# BellSystem.net
KiCad netlist of a schematic drawn in Altium Designer
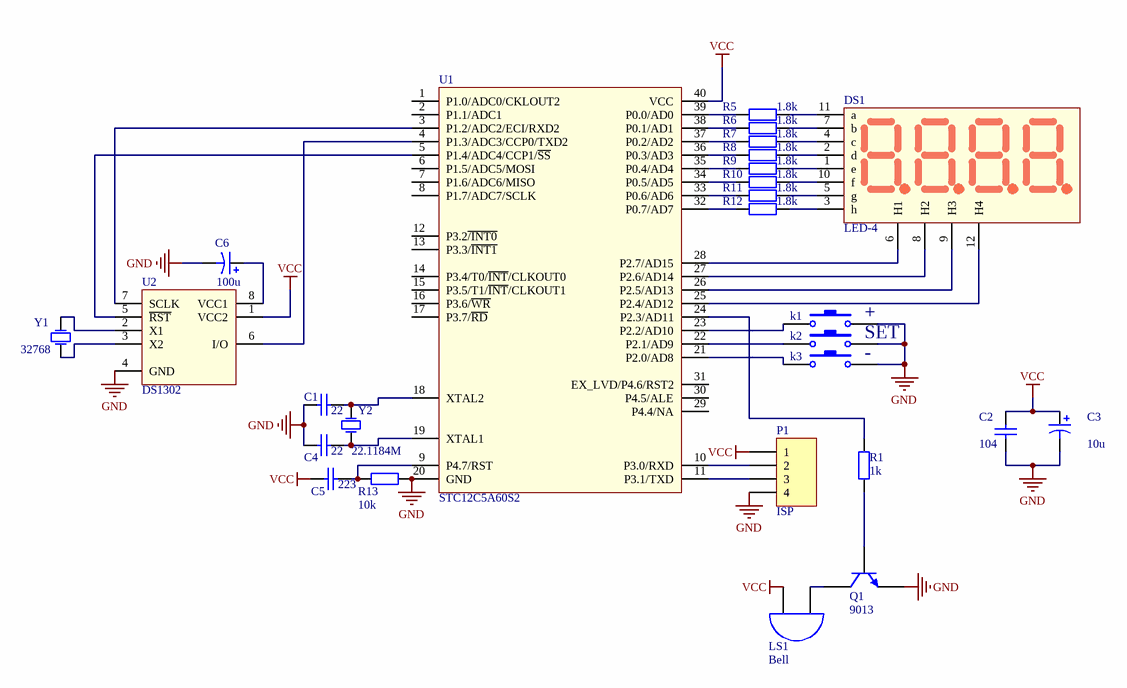
[diagram p0: BellSystem.SchDoc]

(export (version "E")
  (design (tool "Eeschema 10.0.6"))
  (components
    (comp (ref "C1")
      (value "22")
      (footprint "cap")
      (description "Capacitor")
      (fields (field (name "PUBLISHER") "Altium Limited"))
      (libsource (lib "Miscellaneous Devices") (part "Cap"))
    )
    (comp (ref "C2")
      (value "104")
      (footprint "cap")
      (description "Capacitor")
      (fields (field (name "PUBLISHER") "Altium Limited"))
      (libsource (lib "Miscellaneous Devices") (part "Cap"))
    )
    (comp (ref "C3")
      (value "10u")
      (footprint "RB.1/.2")
      (description "Polarized Capacitor (Radial)")
      (fields (field (name "PUBLISHER") "Altium Limited"))
      (libsource (lib "Miscellaneous Devices") (part "Cap Pol1"))
    )
    (comp (ref "C4")
      (value "22")
      (footprint "cap")
      (description "Capacitor")
      (fields (field (name "PUBLISHER") "Altium Limited"))
      (libsource (lib "Miscellaneous Devices") (part "Cap"))
    )
    (comp (ref "C5")
      (value "223")
      (footprint "cap")
      (description "Capacitor")
      (fields (field (name "PUBLISHER") "Altium Limited"))
      (libsource (lib "Miscellaneous Devices") (part "Cap"))
    )
    (comp (ref "C6")
      (value "100u")
      (footprint "RB.1/.2")
      (description "Polarized Capacitor (Radial)")
      (fields (field (name "PUBLISHER") "Altium Limited"))
      (libsource (lib "Miscellaneous Devices") (part "Cap Pol1"))
    )
    (comp (ref "DS1") (value "LED-4") (footprint "7SEG_036x4") (libsource (lib "教学打铃系统") (part "LED-4")))
    (comp (ref "k1")
      (value "+")
      (footprint "SW-4")
      (description "Switch")
      (fields (field (name "PUBLISHER") "Altium Limited"))
      (libsource (lib "Miscellaneous Devices") (part "SW-PB"))
    )
    (comp (ref "k2")
      (value "SET")
      (footprint "SW-4")
      (description "Switch")
      (fields (field (name "PUBLISHER") "Altium Limited"))
      (libsource (lib "Miscellaneous Devices") (part "SW-PB"))
    )
    (comp (ref "k3")
      (value "-")
      (footprint "SW-4")
      (description "Switch")
      (fields (field (name "PUBLISHER") "Altium Limited"))
      (libsource (lib "Miscellaneous Devices") (part "SW-PB"))
    )
    (comp (ref "LS1")
      (value "Bell")
      (footprint "蜂鸣器")
      (description "Electrical Bell")
      (fields (field (name "PUBLISHER") "Altium Limited"))
      (libsource (lib "Miscellaneous Devices") (part "Bell"))
    )
    (comp (ref "P1")
      (value "ISP")
      (footprint "sip4")
      (description "Header, 4-Pin")
      (fields (field (name "PUBLISHER") "Altium Limited"))
      (libsource (lib "Miscellaneous Connectors") (part "Header 4"))
    )
    (comp (ref "Q1")
      (value "9013")
      (footprint "To-92")
      (description "NPN General Purpose Amplifier")
      (fields (field (name "PUBLISHER") "Altium Limited"))
      (libsource (lib "Miscellaneous Devices") (part "2N3904"))
    )
    (comp (ref "R1")
      (value "1k")
      (footprint "AXIAL-0.3")
      (description "Resistor")
      (fields (field (name "PUBLISHER") "Altium Limited"))
      (libsource (lib "Miscellaneous Devices") (part "Res2"))
    )
    (comp (ref "R5")
      (value "1.8k")
      (footprint "AXIAL-0.3")
      (description "Resistor")
      (fields (field (name "PUBLISHER") "Altium Limited"))
      (libsource (lib "") (part "Res2_1"))
    )
    (comp (ref "R6")
      (value "1.8k")
      (footprint "AXIAL-0.3")
      (description "Resistor")
      (fields (field (name "PUBLISHER") "Altium Limited"))
      (libsource (lib "") (part "Res2_1"))
    )
    (comp (ref "R7")
      (value "1.8k")
      (footprint "AXIAL-0.3")
      (description "Resistor")
      (fields (field (name "PUBLISHER") "Altium Limited"))
      (libsource (lib "") (part "Res2_1"))
    )
    (comp (ref "R8")
      (value "1.8k")
      (footprint "AXIAL-0.3")
      (description "Resistor")
      (fields (field (name "PUBLISHER") "Altium Limited"))
      (libsource (lib "") (part "Res2_1"))
    )
    (comp (ref "R9")
      (value "1.8k")
      (footprint "AXIAL-0.3")
      (description "Resistor")
      (fields (field (name "PUBLISHER") "Altium Limited"))
      (libsource (lib "") (part "Res2_1"))
    )
    (comp (ref "R10")
      (value "1.8k")
      (footprint "AXIAL-0.3")
      (description "Resistor")
      (fields (field (name "PUBLISHER") "Altium Limited"))
      (libsource (lib "") (part "Res2_1"))
    )
    (comp (ref "R11")
      (value "1.8k")
      (footprint "AXIAL-0.3")
      (description "Resistor")
      (fields (field (name "PUBLISHER") "Altium Limited"))
      (libsource (lib "") (part "Res2_1"))
    )
    (comp (ref "R12")
      (value "1.8k")
      (footprint "AXIAL-0.3")
      (description "Resistor")
      (fields (field (name "PUBLISHER") "Altium Limited"))
      (libsource (lib "") (part "Res2_1"))
    )
    (comp (ref "R13")
      (value "10k")
      (footprint "AXIAL-0.3")
      (description "Resistor")
      (fields (field (name "PUBLISHER") "Altium Limited"))
      (libsource (lib "") (part "Res2_1"))
    )
    (comp (ref "U1")
      (value "STC12C5A60S2")
      (footprint "STC89C52")
      (libsource (lib "教学打铃系统") (part "STC12C5A60S2"))
    )
    (comp (ref "U2") (value "DS1302") (footprint "DS1302") (libsource (lib "教学打铃系统") (part "DS1302")))
    (comp (ref "Y1")
      (value "32768")
      (footprint "32768")
      (description "Crystal Oscillator")
      (fields (field (name "PUBLISHER") "Altium Limited"))
      (libsource (lib "Miscellaneous Devices") (part "XTAL"))
    )
    (comp (ref "Y2")
      (value "22.1184M")
      (footprint "XTAL")
      (description "Crystal Oscillator")
      (fields (field (name "PUBLISHER") "Altium Limited"))
      (libsource (lib "Miscellaneous Devices") (part "XTAL"))
    )
  )
  (nets
    (net (code "1") (name "GND") (class "Default")
      (node (ref "C1") (pin "1") (pinfunction "1_1") (pintype "passive"))
      (node (ref "C2") (pin "1") (pinfunction "1_1") (pintype "passive"))
      (node (ref "C3") (pin "2") (pinfunction "2_2") (pintype "passive"))
      (node (ref "C4") (pin "1") (pinfunction "1_1") (pintype "passive"))
      (node (ref "C6") (pin "2") (pinfunction "2_2") (pintype "passive"))
      (node (ref "P1") (pin "4") (pinfunction "4_4") (pintype "passive"))
      (node (ref "Q1") (pin "1") (pinfunction "E_1") (pintype "passive"))
      (node (ref "R13") (pin "2") (pinfunction "2_2") (pintype "passive"))
      (node (ref "U1") (pin "20") (pinfunction "GND_20") (pintype "passive"))
      (node (ref "U2") (pin "4") (pinfunction "GND_4") (pintype "passive"))
      (node (ref "k1") (pin "2") (pinfunction "2_2") (pintype "passive"))
      (node (ref "k2") (pin "2") (pinfunction "2_2") (pintype "passive"))
      (node (ref "k3") (pin "2") (pinfunction "2_2") (pintype "passive"))
    )
    (net (code "2") (name "Net-(DS1-H1)") (class "Default")
      (node (ref "DS1") (pin "6") (pinfunction "H1_6") (pintype "passive"))
      (node (ref "U1") (pin "28") (pinfunction "P2.7/AD15_28") (pintype "passive"))
    )
    (net (code "3") (name "Net-(DS1-H2)") (class "Default")
      (node (ref "DS1") (pin "8") (pinfunction "H2_8") (pintype "passive"))
      (node (ref "U1") (pin "27") (pinfunction "P2.6/AD14_27") (pintype "passive"))
    )
    (net (code "4") (name "Net-(DS1-H3)") (class "Default")
      (node (ref "DS1") (pin "9") (pinfunction "H3_9") (pintype "passive"))
      (node (ref "U1") (pin "26") (pinfunction "P2.5/AD13_26") (pintype "passive"))
    )
    (net (code "5") (name "Net-(DS1-H4)") (class "Default")
      (node (ref "DS1") (pin "12") (pinfunction "H4_12") (pintype "passive"))
      (node (ref "U1") (pin "25") (pinfunction "P2.4/AD12_25") (pintype "passive"))
    )
    (net (code "6") (name "Net-(DS1-a)") (class "Default")
      (node (ref "DS1") (pin "11") (pinfunction "a_11") (pintype "passive"))
      (node (ref "R5") (pin "2") (pinfunction "2_2") (pintype "passive"))
    )
    (net (code "7") (name "Net-(DS1-b)") (class "Default")
      (node (ref "DS1") (pin "7") (pinfunction "b_7") (pintype "passive"))
      (node (ref "R6") (pin "2") (pinfunction "2_2") (pintype "passive"))
    )
    (net (code "8") (name "Net-(DS1-c)") (class "Default")
      (node (ref "DS1") (pin "4") (pinfunction "c_4") (pintype "passive"))
      (node (ref "R7") (pin "2") (pinfunction "2_2") (pintype "passive"))
    )
    (net (code "9") (name "Net-(DS1-d)") (class "Default")
      (node (ref "DS1") (pin "2") (pinfunction "d_2") (pintype "passive"))
      (node (ref "R8") (pin "2") (pinfunction "2_2") (pintype "passive"))
    )
    (net (code "10") (name "Net-(DS1-e)") (class "Default")
      (node (ref "DS1") (pin "1") (pinfunction "e_1") (pintype "passive"))
      (node (ref "R9") (pin "2") (pinfunction "2_2") (pintype "passive"))
    )
    (net (code "11") (name "Net-(DS1-f)") (class "Default")
      (node (ref "DS1") (pin "10") (pinfunction "f_10") (pintype "passive"))
      (node (ref "R10") (pin "2") (pinfunction "2_2") (pintype "passive"))
    )
    (net (code "12") (name "Net-(DS1-g)") (class "Default")
      (node (ref "DS1") (pin "5") (pinfunction "g_5") (pintype "passive"))
      (node (ref "R11") (pin "2") (pinfunction "2_2") (pintype "passive"))
    )
    (net (code "13") (name "Net-(DS1-h)") (class "Default")
      (node (ref "DS1") (pin "3") (pinfunction "h_3") (pintype "passive"))
      (node (ref "R12") (pin "2") (pinfunction "2_2") (pintype "passive"))
    )
    (net (code "14") (name "Net-(LS1-B)") (class "Default")
      (node (ref "LS1") (pin "2") (pinfunction "B_2") (pintype "passive"))
      (node (ref "Q1") (pin "3") (pinfunction "C_3") (pintype "passive"))
    )
    (net (code "15") (name "Net-(Q1-B)") (class "Default")
      (node (ref "Q1") (pin "2") (pinfunction "B_2") (pintype "passive"))
      (node (ref "R1") (pin "1") (pinfunction "1_1") (pintype "passive"))
    )
    (net (code "16") (name "Net-(U1-P0.0{slash}AD0)") (class "Default")
      (node (ref "R5") (pin "1") (pinfunction "1_1") (pintype "passive"))
      (node (ref "U1") (pin "39") (pinfunction "P0.0/AD0_39") (pintype "passive"))
    )
    (net (code "17") (name "Net-(U1-P0.1{slash}AD1)") (class "Default")
      (node (ref "R6") (pin "1") (pinfunction "1_1") (pintype "passive"))
      (node (ref "U1") (pin "38") (pinfunction "P0.1/AD1_38") (pintype "passive"))
    )
    (net (code "18") (name "Net-(U1-P0.2{slash}AD2)") (class "Default")
      (node (ref "R7") (pin "1") (pinfunction "1_1") (pintype "passive"))
      (node (ref "U1") (pin "37") (pinfunction "P0.2/AD2_37") (pintype "passive"))
    )
    (net (code "19") (name "Net-(U1-P0.3{slash}AD3)") (class "Default")
      (node (ref "R8") (pin "1") (pinfunction "1_1") (pintype "passive"))
      (node (ref "U1") (pin "36") (pinfunction "P0.3/AD3_36") (pintype "passive"))
    )
    (net (code "20") (name "Net-(U1-P0.4{slash}AD4)") (class "Default")
      (node (ref "R9") (pin "1") (pinfunction "1_1") (pintype "passive"))
      (node (ref "U1") (pin "35") (pinfunction "P0.4/AD4_35") (pintype "passive"))
    )
    (net (code "21") (name "Net-(U1-P0.5{slash}AD5)") (class "Default")
      (node (ref "R10") (pin "1") (pinfunction "1_1") (pintype "passive"))
      (node (ref "U1") (pin "34") (pinfunction "P0.5/AD5_34") (pintype "passive"))
    )
    (net (code "22") (name "Net-(U1-P0.6{slash}AD6)") (class "Default")
      (node (ref "R11") (pin "1") (pinfunction "1_1") (pintype "passive"))
      (node (ref "U1") (pin "33") (pinfunction "P0.6/AD6_33") (pintype "passive"))
    )
    (net (code "23") (name "Net-(U1-P0.7{slash}AD7)") (class "Default")
      (node (ref "R12") (pin "1") (pinfunction "1_1") (pintype "passive"))
      (node (ref "U1") (pin "32") (pinfunction "P0.7/AD7_32") (pintype "passive"))
    )
    (net (code "24") (name "Net-(U1-P1.2{slash}ADC2{slash}ECI{slash}RXD2)") (class "Default")
      (node (ref "U1") (pin "3") (pinfunction "P1.2/ADC2/ECI/RXD2_3") (pintype "passive"))
      (node (ref "U2") (pin "7") (pinfunction "SCLK_7") (pintype "passive"))
    )
    (net (code "25") (name "Net-(U1-P1.3{slash}ADC3{slash}CCP0{slash}TXD2)") (class "Default")
      (node (ref "U1") (pin "4") (pinfunction "P1.3/ADC3/CCP0/TXD2_4") (pintype "passive"))
      (node (ref "U2") (pin "6") (pinfunction "I/O_6") (pintype "passive"))
    )
    (net (code "26") (name "Net-(U1-P1.4{slash}ADC4{slash}CCP1{slash}~{SS})") (class "Default")
      (node (ref "U1") (pin "5") (pinfunction "P1.4/ADC4/CCP1/~{SS}_5") (pintype "passive"))
      (node (ref "U2") (pin "5") (pinfunction "~{RST}_5") (pintype "passive"))
    )
    (net (code "27") (name "Net-(U1-P2.0{slash}AD8)") (class "Default")
      (node (ref "U1") (pin "21") (pinfunction "P2.0/AD8_21") (pintype "passive"))
      (node (ref "k3") (pin "1") (pinfunction "1_1") (pintype "passive"))
    )
    (net (code "28") (name "Net-(U1-P2.1{slash}AD9)") (class "Default")
      (node (ref "U1") (pin "22") (pinfunction "P2.1/AD9_22") (pintype "passive"))
      (node (ref "k2") (pin "1") (pinfunction "1_1") (pintype "passive"))
    )
    (net (code "29") (name "Net-(U1-P2.2{slash}AD10)") (class "Default")
      (node (ref "U1") (pin "23") (pinfunction "P2.2/AD10_23") (pintype "passive"))
      (node (ref "k1") (pin "1") (pinfunction "1_1") (pintype "passive"))
    )
    (net (code "30") (name "Net-(U1-P2.3{slash}AD11)") (class "Default")
      (node (ref "R1") (pin "2") (pinfunction "2_2") (pintype "passive"))
      (node (ref "U1") (pin "24") (pinfunction "P2.3/AD11_24") (pintype "passive"))
    )
    (net (code "31") (name "Net-(U1-P3.0{slash}RXD)") (class "Default")
      (node (ref "P1") (pin "2") (pinfunction "2_2") (pintype "passive"))
      (node (ref "U1") (pin "10") (pinfunction "P3.0/RXD_10") (pintype "passive"))
    )
    (net (code "32") (name "Net-(U1-P3.1{slash}TXD)") (class "Default")
      (node (ref "P1") (pin "3") (pinfunction "3_3") (pintype "passive"))
      (node (ref "U1") (pin "11") (pinfunction "P3.1/TXD_11") (pintype "passive"))
    )
    (net (code "33") (name "Net-(U1-P4.7{slash}RST)") (class "Default")
      (node (ref "C5") (pin "2") (pinfunction "2_2") (pintype "passive"))
      (node (ref "R13") (pin "1") (pinfunction "1_1") (pintype "passive"))
      (node (ref "U1") (pin "9") (pinfunction "P4.7/RST_9") (pintype "passive"))
    )
    (net (code "34") (name "Net-(U1-XTAL1)") (class "Default")
      (node (ref "C4") (pin "2") (pinfunction "2_2") (pintype "passive"))
      (node (ref "U1") (pin "19") (pinfunction "XTAL1_19") (pintype "passive"))
      (node (ref "Y2") (pin "1") (pinfunction "OSC1_1") (pintype "passive"))
    )
    (net (code "35") (name "Net-(U1-XTAL2)") (class "Default")
      (node (ref "C1") (pin "2") (pinfunction "2_2") (pintype "passive"))
      (node (ref "U1") (pin "18") (pinfunction "XTAL2_18") (pintype "passive"))
      (node (ref "Y2") (pin "2") (pinfunction "OSC2_2") (pintype "passive"))
    )
    (net (code "36") (name "Net-(U2-VCC1)") (class "Default")
      (node (ref "C6") (pin "1") (pinfunction "1_1") (pintype "passive"))
      (node (ref "U2") (pin "8") (pinfunction "VCC1_8") (pintype "passive"))
    )
    (net (code "37") (name "Net-(U2-X1)") (class "Default")
      (node (ref "U2") (pin "2") (pinfunction "X1_2") (pintype "passive"))
      (node (ref "Y1") (pin "2") (pinfunction "OSC2_2") (pintype "passive"))
    )
    (net (code "38") (name "Net-(U2-X2)") (class "Default")
      (node (ref "U2") (pin "3") (pinfunction "X2_3") (pintype "passive"))
      (node (ref "Y1") (pin "1") (pinfunction "OSC1_1") (pintype "passive"))
    )
    (net (code "39") (name "VCC") (class "Default")
      (node (ref "C2") (pin "2") (pinfunction "2_2") (pintype "passive"))
      (node (ref "C3") (pin "1") (pinfunction "1_1") (pintype "passive"))
      (node (ref "C5") (pin "1") (pinfunction "1_1") (pintype "passive"))
      (node (ref "LS1") (pin "1") (pinfunction "A_1") (pintype "passive"))
      (node (ref "P1") (pin "1") (pinfunction "1_1") (pintype "passive"))
      (node (ref "U1") (pin "40") (pinfunction "VCC_40") (pintype "passive"))
      (node (ref "U2") (pin "1") (pinfunction "VCC2_1") (pintype "passive"))
    )
    (net (code "40") (name "unconnected-(U1-EX_LVD{slash}P4.6{slash}RST2-Pad31)") (class "Default")
      (node (ref "U1") (pin "31") (pinfunction "EX_LVD/P4.6/RST2_31") (pintype "passive"))
    )
    (net (code "41") (name "unconnected-(U1-P1.0{slash}ADC0{slash}CKLOUT2-Pad1)") (class "Default")
      (node (ref "U1") (pin "1") (pinfunction "P1.0/ADC0/CKLOUT2_1") (pintype "passive"))
    )
    (net (code "42") (name "unconnected-(U1-P1.1{slash}ADC1-Pad2)") (class "Default")
      (node (ref "U1") (pin "2") (pinfunction "P1.1/ADC1_2") (pintype "passive"))
    )
    (net (code "43") (name "unconnected-(U1-P1.5{slash}ADC5{slash}MOSI-Pad6)") (class "Default")
      (node (ref "U1") (pin "6") (pinfunction "P1.5/ADC5/MOSI_6") (pintype "passive"))
    )
    (net (code "44") (name "unconnected-(U1-P1.6{slash}ADC6{slash}MISO-Pad7)") (class "Default")
      (node (ref "U1") (pin "7") (pinfunction "P1.6/ADC6/MISO_7") (pintype "passive"))
    )
    (net (code "45") (name "unconnected-(U1-P1.7{slash}ADC7{slash}SCLK-Pad8)") (class "Default")
      (node (ref "U1") (pin "8") (pinfunction "P1.7/ADC7/SCLK_8") (pintype "passive"))
    )
    (net (code "46") (name "unconnected-(U1-P3.2~{{slash}INT0}-Pad12)") (class "Default")
      (node (ref "U1") (pin "12") (pinfunction "P3.2~{/INT0}_12") (pintype "passive"))
    )
    (net (code "47") (name "unconnected-(U1-P3.3{slash}~{INT1}-Pad13)") (class "Default")
      (node (ref "U1") (pin "13") (pinfunction "P3.3/~{INT1}_13") (pintype "passive"))
    )
    (net (code "48") (name "unconnected-(U1-P3.4{slash}T0{slash}~{INT}{slash}CLKOUT0-Pad14)") (class "Default")
      (node (ref "U1") (pin "14") (pinfunction "P3.4/T0/~{INT}/CLKOUT0_14") (pintype "passive"))
    )
    (net (code "49") (name "unconnected-(U1-P3.5{slash}T1{slash}~{INT}{slash}CLKOUT1-Pad15)") (class "Default")
      (node (ref "U1") (pin "15") (pinfunction "P3.5/T1/~{INT}/CLKOUT1_15") (pintype "passive"))
    )
    (net (code "50") (name "unconnected-(U1-P3.6{slash}~{WR}-Pad16)") (class "Default")
      (node (ref "U1") (pin "16") (pinfunction "P3.6/~{WR}_16") (pintype "passive"))
    )
    (net (code "51") (name "unconnected-(U1-P3.7{slash}~{RD}-Pad17)") (class "Default")
      (node (ref "U1") (pin "17") (pinfunction "P3.7/~{RD}_17") (pintype "passive"))
    )
    (net (code "52") (name "unconnected-(U1-P4.4{slash}NA-Pad29)") (class "Default")
      (node (ref "U1") (pin "29") (pinfunction "P4.4/NA_29") (pintype "passive"))
    )
    (net (code "53") (name "unconnected-(U1-P4.5{slash}ALE-Pad30)") (class "Default")
      (node (ref "U1") (pin "30") (pinfunction "P4.5/ALE_30") (pintype "passive"))
    )
  )
)
